# POWER-BOARD.net
KiCad netlist of a schematic drawn in EAGLE
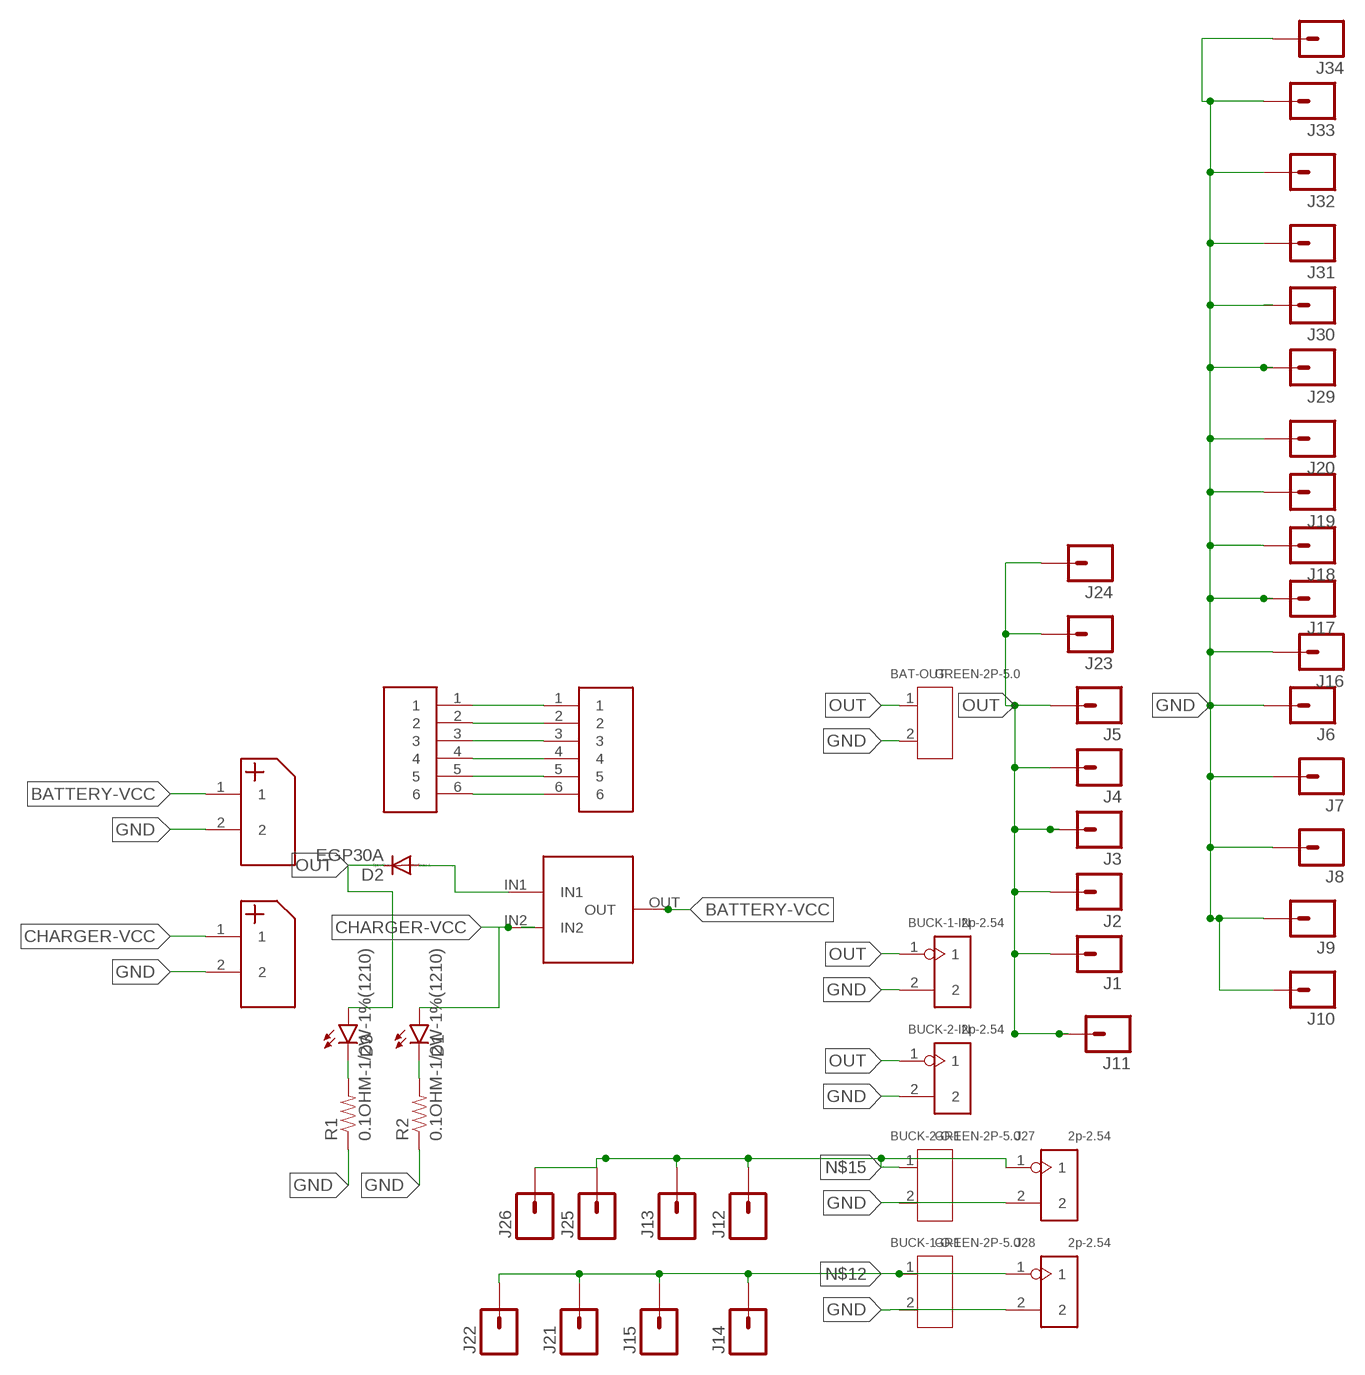
[diagram p0: schematic, sheet 1]

(export (version "E")
  (design (tool "Eeschema 10.0.6"))
  (components
    (comp (ref "BAT-OUT")
      (value "GREEN-2P-5.0")
      (footprint "eagle-import:H2-5.0-10.5X8.0MM")
      (libsource (lib "eagle-import") (part "SCREW-TERMINAL-GREEN(2P-5.0)"))
    )
    (comp (ref "BUCK-1-IN")
      (value "2p-2.54")
      (footprint "eagle-import:H2-2.54")
      (fields (field (name "MPN") "P125-1102A0BS116A1"))
      (libsource (lib "eagle-import") (part "DIP-BLACK-MALE-HEADER-VERT(2P-2.54)"))
    )
    (comp (ref "BUCK-1-O-1")
      (value "GREEN-2P-5.0")
      (footprint "eagle-import:H2-5.0-10.5X8.0MM")
      (libsource (lib "eagle-import") (part "SCREW-TERMINAL-GREEN(2P-5.0)"))
    )
    (comp (ref "BUCK-2-IN")
      (value "2p-2.54")
      (footprint "eagle-import:H2-2.54")
      (fields (field (name "MPN") "P125-1102A0BS116A1"))
      (libsource (lib "eagle-import") (part "DIP-BLACK-MALE-HEADER-VERT(2P-2.54)"))
    )
    (comp (ref "BUCK-2-O-1")
      (value "GREEN-2P-5.0")
      (footprint "eagle-import:H2-5.0-10.5X8.0MM")
      (libsource (lib "eagle-import") (part "SCREW-TERMINAL-GREEN(2P-5.0)"))
    )
    (comp (ref "D1")
      (value "LED-FKIT-1206")
      (footprint "eagle-import:FKIT-LED-1206")
      (libsource (lib "eagle-import") (part "LED-FKIT-1206"))
    )
    (comp (ref "D2")
      (value "EGP30A")
      (footprint "eagle-import:DO201-15")
      (libsource (lib "eagle-import") (part "EGP30A"))
    )
    (comp (ref "D3")
      (value "LED-FKIT-1206")
      (footprint "eagle-import:FKIT-LED-1206")
      (libsource (lib "eagle-import") (part "LED-FKIT-1206"))
    )
    (comp (ref "J1")
      (value "M01PTH")
      (footprint "eagle-import:1X01")
      (libsource (lib "eagle-import") (part "M01PTH"))
    )
    (comp (ref "J2")
      (value "M01PTH")
      (footprint "eagle-import:1X01")
      (libsource (lib "eagle-import") (part "M01PTH"))
    )
    (comp (ref "J3")
      (value "M01PTH")
      (footprint "eagle-import:1X01")
      (libsource (lib "eagle-import") (part "M01PTH"))
    )
    (comp (ref "J4")
      (value "M01PTH")
      (footprint "eagle-import:1X01")
      (libsource (lib "eagle-import") (part "M01PTH"))
    )
    (comp (ref "J5")
      (value "M01PTH")
      (footprint "eagle-import:1X01")
      (libsource (lib "eagle-import") (part "M01PTH"))
    )
    (comp (ref "J6")
      (value "M01PTH")
      (footprint "eagle-import:1X01")
      (libsource (lib "eagle-import") (part "M01PTH"))
    )
    (comp (ref "J7")
      (value "M01PTH")
      (footprint "eagle-import:1X01")
      (libsource (lib "eagle-import") (part "M01PTH"))
    )
    (comp (ref "J8")
      (value "M01PTH")
      (footprint "eagle-import:1X01")
      (libsource (lib "eagle-import") (part "M01PTH"))
    )
    (comp (ref "J9")
      (value "M01PTH")
      (footprint "eagle-import:1X01")
      (libsource (lib "eagle-import") (part "M01PTH"))
    )
    (comp (ref "J10")
      (value "M01PTH")
      (footprint "eagle-import:1X01")
      (libsource (lib "eagle-import") (part "M01PTH"))
    )
    (comp (ref "J11")
      (value "M01PTH")
      (footprint "eagle-import:1X01")
      (libsource (lib "eagle-import") (part "M01PTH"))
    )
    (comp (ref "J12")
      (value "M01PTH")
      (footprint "eagle-import:1X01")
      (libsource (lib "eagle-import") (part "M01PTH"))
    )
    (comp (ref "J13")
      (value "M01PTH")
      (footprint "eagle-import:1X01")
      (libsource (lib "eagle-import") (part "M01PTH"))
    )
    (comp (ref "J14")
      (value "M01PTH")
      (footprint "eagle-import:1X01")
      (libsource (lib "eagle-import") (part "M01PTH"))
    )
    (comp (ref "J15")
      (value "M01PTH")
      (footprint "eagle-import:1X01")
      (libsource (lib "eagle-import") (part "M01PTH"))
    )
    (comp (ref "J16")
      (value "M01PTH")
      (footprint "eagle-import:1X01")
      (libsource (lib "eagle-import") (part "M01PTH"))
    )
    (comp (ref "J17")
      (value "M01PTH")
      (footprint "eagle-import:1X01")
      (libsource (lib "eagle-import") (part "M01PTH"))
    )
    (comp (ref "J18")
      (value "M01PTH")
      (footprint "eagle-import:1X01")
      (libsource (lib "eagle-import") (part "M01PTH"))
    )
    (comp (ref "J19")
      (value "M01PTH")
      (footprint "eagle-import:1X01")
      (libsource (lib "eagle-import") (part "M01PTH"))
    )
    (comp (ref "J20")
      (value "M01PTH")
      (footprint "eagle-import:1X01")
      (libsource (lib "eagle-import") (part "M01PTH"))
    )
    (comp (ref "J21")
      (value "M01PTH")
      (footprint "eagle-import:1X01")
      (libsource (lib "eagle-import") (part "M01PTH"))
    )
    (comp (ref "J22")
      (value "M01PTH")
      (footprint "eagle-import:1X01")
      (libsource (lib "eagle-import") (part "M01PTH"))
    )
    (comp (ref "J23")
      (value "M01PTH")
      (footprint "eagle-import:1X01")
      (libsource (lib "eagle-import") (part "M01PTH"))
    )
    (comp (ref "J24")
      (value "M01PTH")
      (footprint "eagle-import:1X01")
      (libsource (lib "eagle-import") (part "M01PTH"))
    )
    (comp (ref "J25")
      (value "M01PTH")
      (footprint "eagle-import:1X01")
      (libsource (lib "eagle-import") (part "M01PTH"))
    )
    (comp (ref "J26")
      (value "M01PTH")
      (footprint "eagle-import:1X01")
      (libsource (lib "eagle-import") (part "M01PTH"))
    )
    (comp (ref "J27")
      (value "2p-2.54")
      (footprint "eagle-import:H2-2.54")
      (fields (field (name "MPN") "P125-1102A0BS116A1"))
      (libsource (lib "eagle-import") (part "DIP-BLACK-MALE-HEADER-VERT(2P-2.54)"))
    )
    (comp (ref "J28")
      (value "2p-2.54")
      (footprint "eagle-import:H2-2.54")
      (fields (field (name "MPN") "P125-1102A0BS116A1"))
      (libsource (lib "eagle-import") (part "DIP-BLACK-MALE-HEADER-VERT(2P-2.54)"))
    )
    (comp (ref "J29")
      (value "M01PTH")
      (footprint "eagle-import:1X01")
      (libsource (lib "eagle-import") (part "M01PTH"))
    )
    (comp (ref "J30")
      (value "M01PTH")
      (footprint "eagle-import:1X01")
      (libsource (lib "eagle-import") (part "M01PTH"))
    )
    (comp (ref "J31")
      (value "M01PTH")
      (footprint "eagle-import:1X01")
      (libsource (lib "eagle-import") (part "M01PTH"))
    )
    (comp (ref "J32")
      (value "M01PTH")
      (footprint "eagle-import:1X01")
      (libsource (lib "eagle-import") (part "M01PTH"))
    )
    (comp (ref "J33")
      (value "M01PTH")
      (footprint "eagle-import:1X01")
      (libsource (lib "eagle-import") (part "M01PTH"))
    )
    (comp (ref "J34")
      (value "M01PTH")
      (footprint "eagle-import:1X01")
      (libsource (lib "eagle-import") (part "M01PTH"))
    )
    (comp (ref "R1")
      (value "0.1OHM-1/2W-1%(1210)")
      (footprint "eagle-import:1210")
      (libsource (lib "eagle-import") (part "0.1OHM-1/2W-1%(1210)"))
    )
    (comp (ref "R2")
      (value "0.1OHM-1/2W-1%(1210)")
      (footprint "eagle-import:1210")
      (libsource (lib "eagle-import") (part "0.1OHM-1/2W-1%(1210)"))
    )
    (comp (ref "U$1")
      (value "SPDT")
      (footprint "eagle-import:SWITCH")
      (libsource (lib "eagle-import") (part "SPDT"))
    )
    (comp (ref "U$2")
      (value "LIPO-POWER")
      (footprint "eagle-import:LIPO-POWER")
      (libsource (lib "eagle-import") (part "LIPO-POWER"))
    )
    (comp (ref "U$3")
      (value "LIPO-POWER")
      (footprint "eagle-import:LIPO-POWER")
      (libsource (lib "eagle-import") (part "LIPO-POWER"))
    )
    (comp (ref "U$4")
      (value "LIPO-CHARGING")
      (footprint "eagle-import:CHARGING-CONN")
      (libsource (lib "eagle-import") (part "LIPO-CHARGING"))
    )
    (comp (ref "U$5")
      (value "LIPO-CHARGING")
      (footprint "eagle-import:CHARGING-CONN")
      (libsource (lib "eagle-import") (part "LIPO-CHARGING"))
    )
  )
  (nets
    (net (code "1") (name "BATTERY-VCC") (class "Default")
      (node (ref "U$1") (pin "OUT") (pinfunction "OUT_OUT") (pintype "bidirectional"))
      (node (ref "U$2") (pin "1") (pinfunction "1_1") (pintype "bidirectional"))
    )
    (net (code "2") (name "CHARGER-VCC") (class "Default")
      (node (ref "D1") (pin "A") (pinfunction "A_A") (pintype "passive"))
      (node (ref "U$1") (pin "IN2") (pinfunction "IN2_IN2") (pintype "bidirectional"))
      (node (ref "U$3") (pin "1") (pinfunction "1_1") (pintype "bidirectional"))
    )
    (net (code "3") (name "GND") (class "Default")
      (node (ref "BAT-OUT") (pin "2") (pinfunction "2_2") (pintype "bidirectional"))
      (node (ref "BUCK-1-IN") (pin "2") (pinfunction "2_2") (pintype "bidirectional"))
      (node (ref "BUCK-1-O-1") (pin "2") (pinfunction "2_2") (pintype "bidirectional"))
      (node (ref "BUCK-2-IN") (pin "2") (pinfunction "2_2") (pintype "bidirectional"))
      (node (ref "BUCK-2-O-1") (pin "2") (pinfunction "2_2") (pintype "bidirectional"))
      (node (ref "J10") (pin "1") (pinfunction "1_1") (pintype "passive"))
      (node (ref "J16") (pin "1") (pinfunction "1_1") (pintype "passive"))
      (node (ref "J17") (pin "1") (pinfunction "1_1") (pintype "passive"))
      (node (ref "J18") (pin "1") (pinfunction "1_1") (pintype "passive"))
      (node (ref "J19") (pin "1") (pinfunction "1_1") (pintype "passive"))
      (node (ref "J20") (pin "1") (pinfunction "1_1") (pintype "passive"))
      (node (ref "J27") (pin "2") (pinfunction "2_2") (pintype "bidirectional"))
      (node (ref "J28") (pin "2") (pinfunction "2_2") (pintype "bidirectional"))
      (node (ref "J29") (pin "1") (pinfunction "1_1") (pintype "passive"))
      (node (ref "J30") (pin "1") (pinfunction "1_1") (pintype "passive"))
      (node (ref "J31") (pin "1") (pinfunction "1_1") (pintype "passive"))
      (node (ref "J32") (pin "1") (pinfunction "1_1") (pintype "passive"))
      (node (ref "J33") (pin "1") (pinfunction "1_1") (pintype "passive"))
      (node (ref "J34") (pin "1") (pinfunction "1_1") (pintype "passive"))
      (node (ref "J6") (pin "1") (pinfunction "1_1") (pintype "passive"))
      (node (ref "J7") (pin "1") (pinfunction "1_1") (pintype "passive"))
      (node (ref "J8") (pin "1") (pinfunction "1_1") (pintype "passive"))
      (node (ref "J9") (pin "1") (pinfunction "1_1") (pintype "passive"))
      (node (ref "R1") (pin "1") (pinfunction "1_1") (pintype "passive"))
      (node (ref "R2") (pin "1") (pinfunction "1_1") (pintype "passive"))
      (node (ref "U$2") (pin "2") (pinfunction "2_2") (pintype "bidirectional"))
      (node (ref "U$3") (pin "2") (pinfunction "2_2") (pintype "bidirectional"))
    )
    (net (code "4") (name "N$12") (class "Default")
      (node (ref "BUCK-1-O-1") (pin "1") (pinfunction "1_1") (pintype "bidirectional"))
      (node (ref "J14") (pin "1") (pinfunction "1_1") (pintype "passive"))
      (node (ref "J15") (pin "1") (pinfunction "1_1") (pintype "passive"))
      (node (ref "J21") (pin "1") (pinfunction "1_1") (pintype "passive"))
      (node (ref "J22") (pin "1") (pinfunction "1_1") (pintype "passive"))
      (node (ref "J28") (pin "1") (pinfunction "1_1") (pintype "bidirectional"))
    )
    (net (code "5") (name "N$15") (class "Default")
      (node (ref "BUCK-2-O-1") (pin "1") (pinfunction "1_1") (pintype "bidirectional"))
      (node (ref "J12") (pin "1") (pinfunction "1_1") (pintype "passive"))
      (node (ref "J13") (pin "1") (pinfunction "1_1") (pintype "passive"))
      (node (ref "J25") (pin "1") (pinfunction "1_1") (pintype "passive"))
      (node (ref "J26") (pin "1") (pinfunction "1_1") (pintype "passive"))
      (node (ref "J27") (pin "1") (pinfunction "1_1") (pintype "bidirectional"))
    )
    (net (code "6") (name "Net-(D1-PadC)") (class "Default")
      (node (ref "D1") (pin "C") (pinfunction "C_C") (pintype "passive"))
      (node (ref "R2") (pin "2") (pinfunction "2_2") (pintype "passive"))
    )
    (net (code "7") (name "Net-(D2-PadA)") (class "Default")
      (node (ref "D2") (pin "A") (pinfunction "A_A") (pintype "passive"))
      (node (ref "U$1") (pin "IN1") (pinfunction "IN1_IN1") (pintype "bidirectional"))
    )
    (net (code "8") (name "Net-(D3-PadC)") (class "Default")
      (node (ref "D3") (pin "C") (pinfunction "C_C") (pintype "passive"))
      (node (ref "R1") (pin "2") (pinfunction "2_2") (pintype "passive"))
    )
    (net (code "9") (name "Net-(U$4-Pad1)") (class "Default")
      (node (ref "U$4") (pin "1") (pinfunction "1_1") (pintype "bidirectional"))
      (node (ref "U$5") (pin "1") (pinfunction "1_1") (pintype "bidirectional"))
    )
    (net (code "10") (name "Net-(U$4-Pad2)") (class "Default")
      (node (ref "U$4") (pin "2") (pinfunction "2_2") (pintype "bidirectional"))
      (node (ref "U$5") (pin "2") (pinfunction "2_2") (pintype "bidirectional"))
    )
    (net (code "11") (name "Net-(U$4-Pad3)") (class "Default")
      (node (ref "U$4") (pin "3") (pinfunction "3_3") (pintype "bidirectional"))
      (node (ref "U$5") (pin "3") (pinfunction "3_3") (pintype "bidirectional"))
    )
    (net (code "12") (name "Net-(U$4-Pad4)") (class "Default")
      (node (ref "U$4") (pin "4") (pinfunction "4_4") (pintype "bidirectional"))
      (node (ref "U$5") (pin "4") (pinfunction "4_4") (pintype "bidirectional"))
    )
    (net (code "13") (name "Net-(U$4-Pad5)") (class "Default")
      (node (ref "U$4") (pin "5") (pinfunction "5_5") (pintype "bidirectional"))
      (node (ref "U$5") (pin "5") (pinfunction "5_5") (pintype "bidirectional"))
    )
    (net (code "14") (name "Net-(U$4-Pad6)") (class "Default")
      (node (ref "U$4") (pin "6") (pinfunction "6_6") (pintype "bidirectional"))
      (node (ref "U$5") (pin "6") (pinfunction "6_6") (pintype "bidirectional"))
    )
    (net (code "15") (name "OUT") (class "Default")
      (node (ref "BAT-OUT") (pin "1") (pinfunction "1_1") (pintype "bidirectional"))
      (node (ref "BUCK-1-IN") (pin "1") (pinfunction "1_1") (pintype "bidirectional"))
      (node (ref "BUCK-2-IN") (pin "1") (pinfunction "1_1") (pintype "bidirectional"))
      (node (ref "D2") (pin "C") (pinfunction "C_C") (pintype "passive"))
      (node (ref "D3") (pin "A") (pinfunction "A_A") (pintype "passive"))
      (node (ref "J1") (pin "1") (pinfunction "1_1") (pintype "passive"))
      (node (ref "J11") (pin "1") (pinfunction "1_1") (pintype "passive"))
      (node (ref "J2") (pin "1") (pinfunction "1_1") (pintype "passive"))
      (node (ref "J23") (pin "1") (pinfunction "1_1") (pintype "passive"))
      (node (ref "J24") (pin "1") (pinfunction "1_1") (pintype "passive"))
      (node (ref "J3") (pin "1") (pinfunction "1_1") (pintype "passive"))
      (node (ref "J4") (pin "1") (pinfunction "1_1") (pintype "passive"))
      (node (ref "J5") (pin "1") (pinfunction "1_1") (pintype "passive"))
    )
  )
)
